# PiInTheSky-Mainboard-v2_4.net
KiCad netlist of a schematic drawn in EAGLE
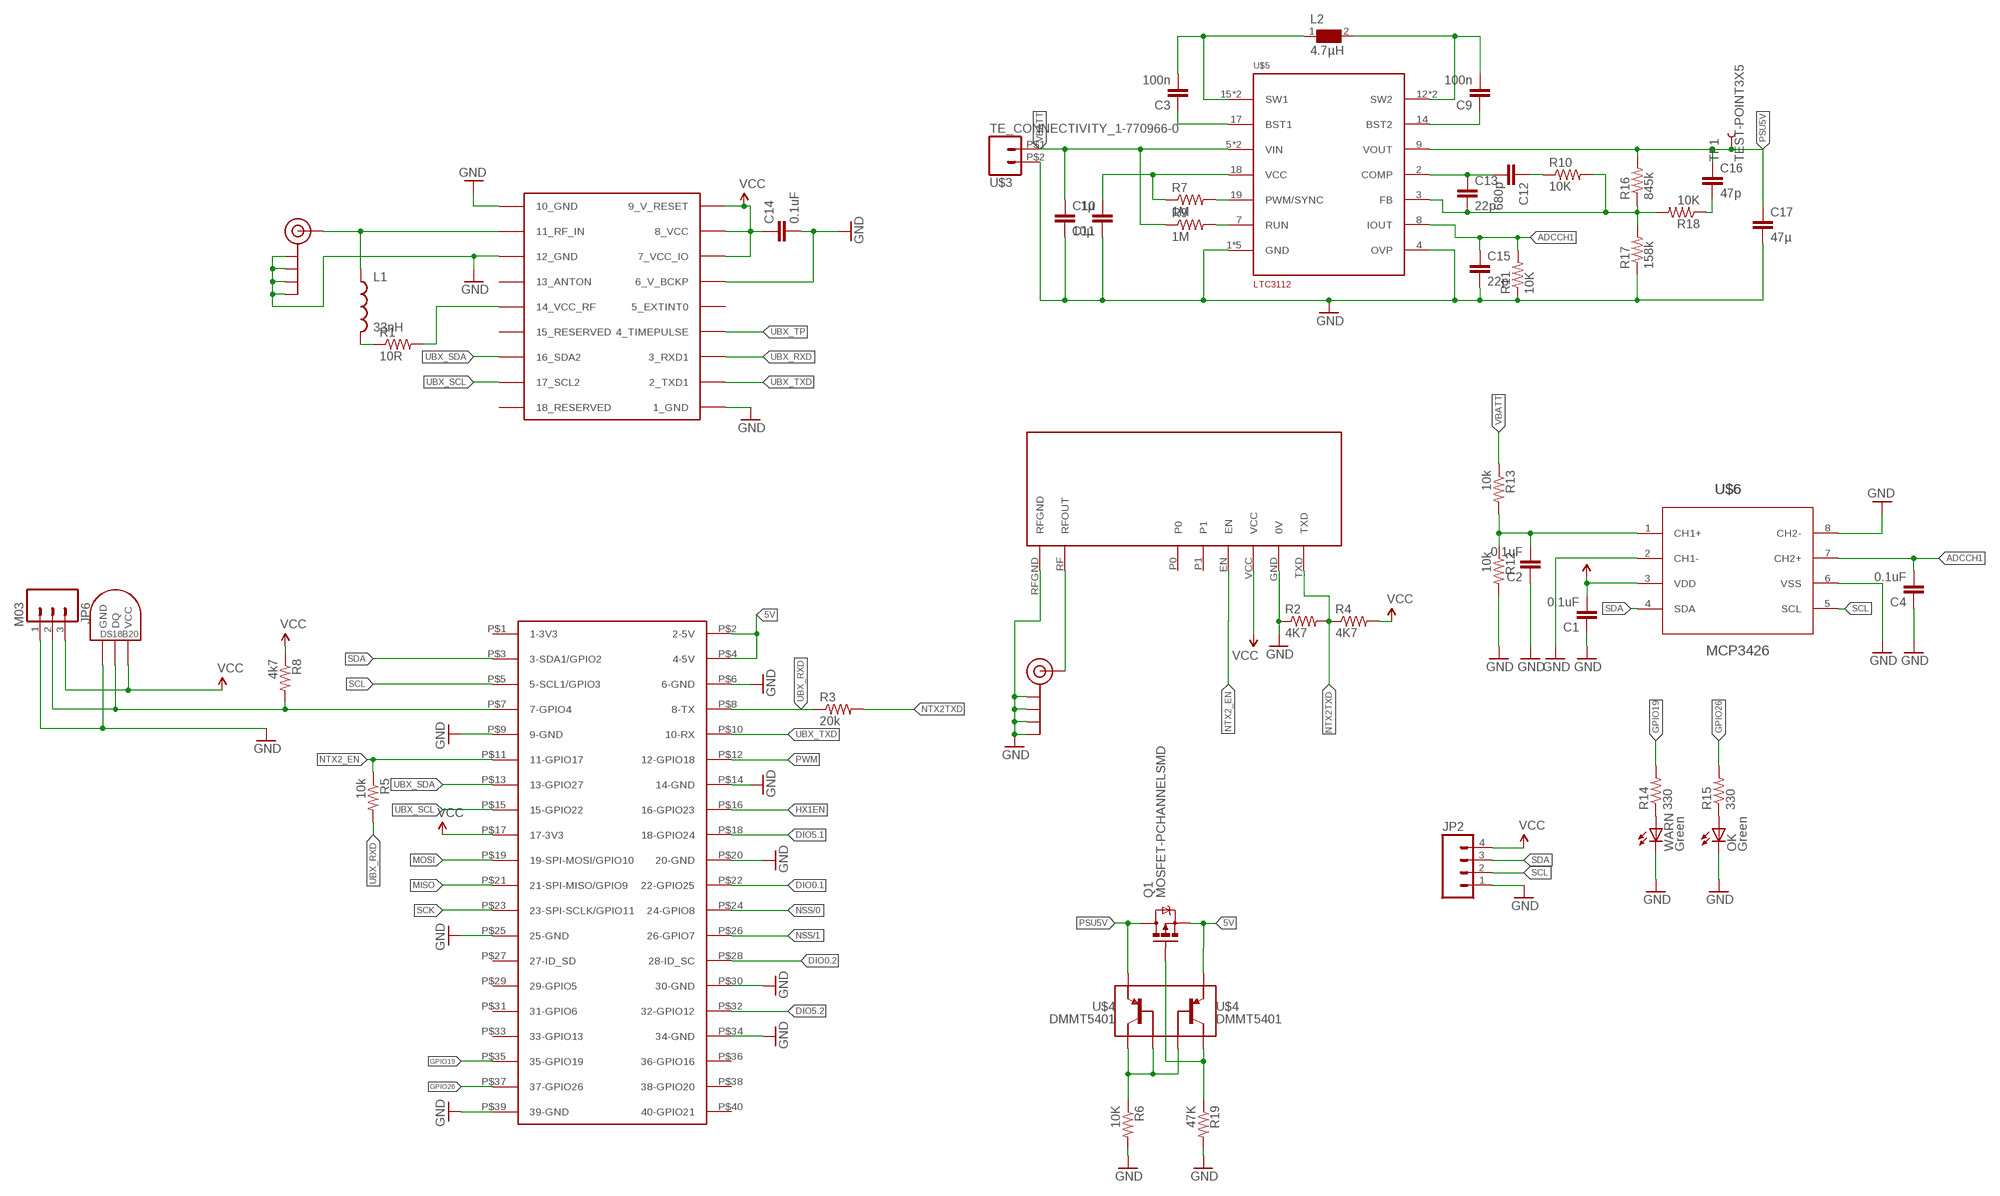
[diagram p0: schematic, sheet 1]

(export (version "E")
  (design (tool "Eeschema 10.0.6"))
  (components
    (comp (ref "C1")
      (value "0.1uF")
      (footprint "eagle-import:0603-CAP")
      (libsource (lib "eagle-import") (part "CAP0603-CAP"))
    )
    (comp (ref "C2")
      (value "0.1uF")
      (footprint "eagle-import:0603-CAP")
      (libsource (lib "eagle-import") (part "CAP0603-CAP"))
    )
    (comp (ref "C3")
      (value "100n")
      (footprint "eagle-import:0603-CAP")
      (libsource (lib "eagle-import") (part "CAP0603-CAP"))
    )
    (comp (ref "C4")
      (value "0.1uF")
      (footprint "eagle-import:0603-CAP")
      (libsource (lib "eagle-import") (part "CAP0603-CAP"))
    )
    (comp (ref "C9")
      (value "100n")
      (footprint "eagle-import:0603-CAP")
      (libsource (lib "eagle-import") (part "CAP0603-CAP"))
    )
    (comp (ref "C10")
      (value "10µ")
      (footprint "eagle-import:1206")
      (libsource (lib "eagle-import") (part "CAP1206"))
    )
    (comp (ref "C11")
      (value "1µ")
      (footprint "eagle-import:0603-CAP")
      (libsource (lib "eagle-import") (part "CAP0603-CAP"))
    )
    (comp (ref "C12")
      (value "680p")
      (footprint "eagle-import:0603-CAP")
      (libsource (lib "eagle-import") (part "CAP0603-CAP"))
    )
    (comp (ref "C13")
      (value "22p")
      (footprint "eagle-import:0603-CAP")
      (libsource (lib "eagle-import") (part "CAP0603-CAP"))
    )
    (comp (ref "C14")
      (value "0.1uF")
      (footprint "eagle-import:0603-CAP")
      (libsource (lib "eagle-import") (part "CAP0603-CAP"))
    )
    (comp (ref "C15")
      (value "22p")
      (footprint "eagle-import:0603-CAP")
      (libsource (lib "eagle-import") (part "CAP0603-CAP"))
    )
    (comp (ref "C16")
      (value "47p")
      (footprint "eagle-import:0603-CAP")
      (libsource (lib "eagle-import") (part "CAP0603-CAP"))
    )
    (comp (ref "C17")
      (value "47µ")
      (footprint "eagle-import:1206")
      (libsource (lib "eagle-import") (part "CAP1206"))
    )
    (comp (ref "J$1")
      (value "SMA_EDGE")
      (footprint "eagle-import:SMA-EDGE")
      (libsource (lib "eagle-import") (part "SMA_EDGE"))
    )
    (comp (ref "J$2")
      (value "SMA_EDGE")
      (footprint "eagle-import:SMA-EDGE")
      (libsource (lib "eagle-import") (part "SMA_EDGE"))
    )
    (comp (ref "JP2")
      (value "M04PTH")
      (footprint "eagle-import:1X04")
      (libsource (lib "eagle-import") (part "M04PTH"))
    )
    (comp (ref "JP6")
      (value "M03")
      (footprint "eagle-import:M03-JST")
      (libsource (lib "eagle-import") (part "M03"))
    )
    (comp (ref "L1")
      (value "33nH")
      (footprint "eagle-import:0603")
      (libsource (lib "eagle-import") (part "INDUCTOR0603"))
    )
    (comp (ref "L2")
      (value "4.7µH")
      (footprint "eagle-import:WE-HCI_7030_7040_7050")
      (fields (field (name "MPN") "744311470"))
      (libsource (lib "eagle-import") (part "WE-HCI_7030/7040/7050-744311470"))
    )
    (comp (ref "OK")
      (value "Green")
      (footprint "eagle-import:LED-0603")
      (libsource (lib "eagle-import") (part "LED0603"))
    )
    (comp (ref "Q1")
      (value "MOSFET-PCHANNELSMD")
      (footprint "eagle-import:SOT23-3")
      (libsource (lib "eagle-import") (part "MOSFET-PCHANNELSMD"))
    )
    (comp (ref "R1")
      (value "10R")
      (footprint "eagle-import:0603-RES")
      (libsource (lib "eagle-import") (part "RESISTOR0603-RES"))
    )
    (comp (ref "R2")
      (value "4K7")
      (footprint "eagle-import:0603-RES")
      (libsource (lib "eagle-import") (part "RESISTOR0603-RES"))
    )
    (comp (ref "R3")
      (value "20k")
      (footprint "eagle-import:0603-RES")
      (libsource (lib "eagle-import") (part "RESISTOR0603-RES"))
    )
    (comp (ref "R4")
      (value "4K7")
      (footprint "eagle-import:0603-RES")
      (libsource (lib "eagle-import") (part "RESISTOR0603-RES"))
    )
    (comp (ref "R5")
      (value "10k")
      (footprint "eagle-import:0603-RES")
      (libsource (lib "eagle-import") (part "RESISTOR0603-RES"))
    )
    (comp (ref "R6")
      (value "10K")
      (footprint "eagle-import:0603-RES")
      (libsource (lib "eagle-import") (part "RESISTOR0603-RES"))
    )
    (comp (ref "R7")
      (value "1M")
      (footprint "eagle-import:0603-RES")
      (libsource (lib "eagle-import") (part "RESISTOR0603-RES"))
    )
    (comp (ref "R8")
      (value "4k7")
      (footprint "eagle-import:0603-RES")
      (libsource (lib "eagle-import") (part "RESISTOR0603-RES"))
    )
    (comp (ref "R9")
      (value "1M")
      (footprint "eagle-import:0603-RES")
      (libsource (lib "eagle-import") (part "RESISTOR0603-RES"))
    )
    (comp (ref "R10")
      (value "10K")
      (footprint "eagle-import:0603-RES")
      (libsource (lib "eagle-import") (part "RESISTOR0603-RES"))
    )
    (comp (ref "R11")
      (value "10K")
      (footprint "eagle-import:0603-RES")
      (libsource (lib "eagle-import") (part "RESISTOR0603-RES"))
    )
    (comp (ref "R12")
      (value "10k")
      (footprint "eagle-import:0603-RES")
      (libsource (lib "eagle-import") (part "RESISTOR0603-RES"))
    )
    (comp (ref "R13")
      (value "10k")
      (footprint "eagle-import:0603-RES")
      (libsource (lib "eagle-import") (part "RESISTOR0603-RES"))
    )
    (comp (ref "R14")
      (value "330")
      (footprint "eagle-import:0603-RES")
      (libsource (lib "eagle-import") (part "RESISTOR0603-RES"))
    )
    (comp (ref "R15")
      (value "330")
      (footprint "eagle-import:0603-RES")
      (libsource (lib "eagle-import") (part "RESISTOR0603-RES"))
    )
    (comp (ref "R16")
      (value "845k")
      (footprint "eagle-import:0603-RES")
      (libsource (lib "eagle-import") (part "RESISTOR0603-RES"))
    )
    (comp (ref "R17")
      (value "158k")
      (footprint "eagle-import:0603-RES")
      (libsource (lib "eagle-import") (part "RESISTOR0603-RES"))
    )
    (comp (ref "R18")
      (value "10K")
      (footprint "eagle-import:0603-RES")
      (libsource (lib "eagle-import") (part "RESISTOR0603-RES"))
    )
    (comp (ref "R19")
      (value "47K")
      (footprint "eagle-import:0603-RES")
      (libsource (lib "eagle-import") (part "RESISTOR0603-RES"))
    )
    (comp (ref "TEMP")
      (value "DS1821")
      (footprint "eagle-import:DS18B20_SOIC")
      (libsource (lib "eagle-import") (part "DS1820SOIC"))
    )
    (comp (ref "TP1")
      (value "TEST-POINT3X5")
      (footprint "eagle-import:PAD.03X.05")
      (libsource (lib "eagle-import") (part "TEST-POINT3X5"))
    )
    (comp (ref "U$1")
      (value "RASPBERRY-PI+")
      (footprint "eagle-import:RASPBERRY-PI-PLUS-CAM_NOTCH")
      (libsource (lib "eagle-import") (part "RASPBERRY-PI+"))
    )
    (comp (ref "U$3")
      (value "TE_CONNECTIVITY_1-770966-0")
      (footprint "eagle-import:TE_CONNECTIVITY_1-770966-0")
      (libsource (lib "eagle-import") (part "TE_CONNECTIVITY_1-770966-0"))
    )
    (comp (ref "U$4")
      (value "DMMT5401")
      (footprint "eagle-import:SOT26")
      (libsource (lib "eagle-import") (part "DMMT5401"))
    )
    (comp (ref "U$5")
      (value "LTC3112")
      (footprint "eagle-import:TSSOP-20")
      (libsource (lib "eagle-import") (part "LTC3112"))
    )
    (comp (ref "U$6")
      (value "MCP3426")
      (footprint "eagle-import:SOIC127P600X175-8N")
      (libsource (lib "eagle-import") (part "MCP3426"))
    )
    (comp (ref "U$7")
      (value "UBLOX_MAX")
      (footprint "eagle-import:UBLOX_MAX")
      (libsource (lib "eagle-import") (part "UBLOX_MAX"))
    )
    (comp (ref "U$8")
      (value "RADIOMETRIX-MTX2")
      (footprint "eagle-import:RADIOMETRIX-MTX2")
      (libsource (lib "eagle-import") (part "RADIOMETRIX-MTX2"))
    )
    (comp (ref "WARN")
      (value "Green")
      (footprint "eagle-import:LED-0603")
      (libsource (lib "eagle-import") (part "LED0603"))
    )
  )
  (nets
    (net (code "1") (name "5V") (class "Default")
      (node (ref "Q1") (pin "2") (pinfunction "S_2") (pintype "passive"))
      (node (ref "U$1") (pin "P$2") (pinfunction "2-5V_P$2") (pintype "bidirectional"))
      (node (ref "U$1") (pin "P$4") (pinfunction "4-5V_P$4") (pintype "bidirectional"))
      (node (ref "U$4") (pin "5") (pinfunction "E2_5") (pintype "passive"))
    )
    (net (code "2") (name "ADCCH1") (class "Default")
      (node (ref "C15") (pin "1") (pinfunction "1_1") (pintype "passive"))
      (node (ref "C4") (pin "2") (pinfunction "2_2") (pintype "passive"))
      (node (ref "R11") (pin "2") (pinfunction "2_2") (pintype "passive"))
      (node (ref "U$5") (pin "8") (pinfunction "IOUT_8") (pintype "bidirectional"))
      (node (ref "U$6") (pin "7") (pinfunction "CH2+_7") (pintype "input"))
    )
    (net (code "3") (name "DIO0.1") (class "Default")
      (node (ref "U$1") (pin "P$22") (pinfunction "22-GPIO25_P$22") (pintype "bidirectional"))
    )
    (net (code "4") (name "DIO0.2") (class "Default")
      (node (ref "U$1") (pin "P$28") (pinfunction "28-ID_SC_P$28") (pintype "bidirectional"))
    )
    (net (code "5") (name "DIO5.1") (class "Default")
      (node (ref "U$1") (pin "P$18") (pinfunction "18-GPIO24_P$18") (pintype "bidirectional"))
    )
    (net (code "6") (name "DIO5.2") (class "Default")
      (node (ref "U$1") (pin "P$32") (pinfunction "32-GPIO12_P$32") (pintype "bidirectional"))
    )
    (net (code "7") (name "GND") (class "Default")
      (node (ref "C1") (pin "1") (pinfunction "1_1") (pintype "passive"))
      (node (ref "C10") (pin "2") (pinfunction "2_2") (pintype "passive"))
      (node (ref "C11") (pin "1") (pinfunction "1_1") (pintype "passive"))
      (node (ref "C14") (pin "2") (pinfunction "2_2") (pintype "passive"))
      (node (ref "C15") (pin "2") (pinfunction "2_2") (pintype "passive"))
      (node (ref "C17") (pin "2") (pinfunction "2_2") (pintype "passive"))
      (node (ref "C2") (pin "1") (pinfunction "1_1") (pintype "passive"))
      (node (ref "C4") (pin "1") (pinfunction "1_1") (pintype "passive"))
      (node (ref "J$1") (pin "GND@0") (pinfunction "GND_GND@0") (pintype "bidirectional"))
      (node (ref "J$1") (pin "GND@1") (pinfunction "GND_GND@1") (pintype "bidirectional"))
      (node (ref "J$1") (pin "GND@2") (pinfunction "GND_GND@2") (pintype "bidirectional"))
      (node (ref "J$1") (pin "GND@3") (pinfunction "GND_GND@3") (pintype "bidirectional"))
      (node (ref "J$2") (pin "GND@0") (pinfunction "GND_GND@0") (pintype "bidirectional"))
      (node (ref "J$2") (pin "GND@1") (pinfunction "GND_GND@1") (pintype "bidirectional"))
      (node (ref "J$2") (pin "GND@2") (pinfunction "GND_GND@2") (pintype "bidirectional"))
      (node (ref "J$2") (pin "GND@3") (pinfunction "GND_GND@3") (pintype "bidirectional"))
      (node (ref "JP2") (pin "1") (pinfunction "1_1") (pintype "passive"))
      (node (ref "JP6") (pin "1") (pinfunction "1_1") (pintype "passive"))
      (node (ref "OK") (pin "C") (pinfunction "C_C") (pintype "passive"))
      (node (ref "R11") (pin "1") (pinfunction "1_1") (pintype "passive"))
      (node (ref "R12") (pin "2") (pinfunction "2_2") (pintype "passive"))
      (node (ref "R17") (pin "1") (pinfunction "1_1") (pintype "passive"))
      (node (ref "R19") (pin "2") (pinfunction "2_2") (pintype "passive"))
      (node (ref "R2") (pin "1") (pinfunction "1_1") (pintype "passive"))
      (node (ref "R6") (pin "2") (pinfunction "2_2") (pintype "passive"))
      (node (ref "TEMP") (pin "GND") (pinfunction "GND_GND") (pintype "power_in"))
      (node (ref "U$1") (pin "P$14") (pinfunction "14-GND_P$14") (pintype "bidirectional"))
      (node (ref "U$1") (pin "P$20") (pinfunction "20-GND_P$20") (pintype "bidirectional"))
      (node (ref "U$1") (pin "P$25") (pinfunction "25-GND_P$25") (pintype "bidirectional"))
      (node (ref "U$1") (pin "P$30") (pinfunction "30-GND_P$30") (pintype "bidirectional"))
      (node (ref "U$1") (pin "P$34") (pinfunction "34-GND_P$34") (pintype "bidirectional"))
      (node (ref "U$1") (pin "P$39") (pinfunction "39-GND_P$39") (pintype "bidirectional"))
      (node (ref "U$1") (pin "P$6") (pinfunction "6-GND_P$6") (pintype "bidirectional"))
      (node (ref "U$1") (pin "P$9") (pinfunction "9-GND_P$9") (pintype "bidirectional"))
      (node (ref "U$3") (pin "P$2") (pinfunction "2_P$2") (pintype "passive"))
      (node (ref "U$5") (pin "1") (pinfunction "GND_1") (pintype "bidirectional"))
      (node (ref "U$5") (pin "10") (pinfunction "GND_10") (pintype "bidirectional"))
      (node (ref "U$5") (pin "11") (pinfunction "GND_11") (pintype "bidirectional"))
      (node (ref "U$5") (pin "20") (pinfunction "GND_20") (pintype "bidirectional"))
      (node (ref "U$5") (pin "21") (pinfunction "GND_21") (pintype "bidirectional"))
      (node (ref "U$5") (pin "4") (pinfunction "OVP_4") (pintype "bidirectional"))
      (node (ref "U$6") (pin "2") (pinfunction "CH1-_2") (pintype "input"))
      (node (ref "U$6") (pin "6") (pinfunction "VSS_6") (pintype "power_in"))
      (node (ref "U$6") (pin "8") (pinfunction "CH2-_8") (pintype "input"))
      (node (ref "U$7") (pin "10_GND") (pinfunction "10_GND_10_GND") (pintype "power_in"))
      (node (ref "U$7") (pin "12_GND") (pinfunction "12_GND_12_GND") (pintype "power_in"))
      (node (ref "U$7") (pin "1_GND") (pinfunction "1_GND_1_GND") (pintype "power_in"))
      (node (ref "U$7") (pin "6_V_BCKP") (pinfunction "6_V_BCKP_6_V_BCKP") (pintype "bidirectional"))
      (node (ref "U$8") (pin "GND") (pinfunction "0V_GND") (pintype "bidirectional"))
      (node (ref "U$8") (pin "RFGND") (pinfunction "RFGND_RFGND") (pintype "bidirectional"))
      (node (ref "WARN") (pin "C") (pinfunction "C_C") (pintype "passive"))
    )
    (net (code "8") (name "GPIO19") (class "Default")
      (node (ref "R14") (pin "2") (pinfunction "2_2") (pintype "passive"))
      (node (ref "U$1") (pin "P$35") (pinfunction "35-GPIO19_P$35") (pintype "bidirectional"))
    )
    (net (code "9") (name "GPIO26") (class "Default")
      (node (ref "R15") (pin "2") (pinfunction "2_2") (pintype "passive"))
      (node (ref "U$1") (pin "P$37") (pinfunction "37-GPIO26_P$37") (pintype "bidirectional"))
    )
    (net (code "10") (name "HX1EN") (class "Default")
      (node (ref "U$1") (pin "P$16") (pinfunction "16-GPIO23_P$16") (pintype "bidirectional"))
    )
    (net (code "11") (name "MISO") (class "Default")
      (node (ref "U$1") (pin "P$21") (pinfunction "21-SPI-MISO/GPIO9_P$21") (pintype "bidirectional"))
    )
    (net (code "12") (name "MOSI") (class "Default")
      (node (ref "U$1") (pin "P$19") (pinfunction "19-SPI-MOSI/GPIO10_P$19") (pintype "bidirectional"))
    )
    (net (code "13") (name "NSS{slash}0") (class "Default")
      (node (ref "U$1") (pin "P$24") (pinfunction "24-GPIO8_P$24") (pintype "bidirectional"))
    )
    (net (code "14") (name "NSS{slash}1") (class "Default")
      (node (ref "U$1") (pin "P$26") (pinfunction "26-GPIO7_P$26") (pintype "bidirectional"))
    )
    (net (code "15") (name "NTX2TXD") (class "Default")
      (node (ref "R2") (pin "2") (pinfunction "2_2") (pintype "passive"))
      (node (ref "R3") (pin "2") (pinfunction "2_2") (pintype "passive"))
      (node (ref "R4") (pin "1") (pinfunction "1_1") (pintype "passive"))
      (node (ref "U$8") (pin "TXD") (pinfunction "TXD_TXD") (pintype "bidirectional"))
    )
    (net (code "16") (name "NTX2_EN") (class "Default")
      (node (ref "R5") (pin "1") (pinfunction "1_1") (pintype "passive"))
      (node (ref "U$1") (pin "P$11") (pinfunction "11-GPIO17_P$11") (pintype "bidirectional"))
      (node (ref "U$8") (pin "EN") (pinfunction "EN_EN") (pintype "bidirectional"))
    )
    (net (code "17") (name "Net-(C3-Pad2)") (class "Default")
      (node (ref "C3") (pin "2") (pinfunction "2_2") (pintype "passive"))
      (node (ref "L2") (pin "1") (pinfunction "1_1") (pintype "passive"))
      (node (ref "U$5") (pin "15") (pinfunction "SW1_15") (pintype "bidirectional"))
      (node (ref "U$5") (pin "16") (pinfunction "SW1_16") (pintype "bidirectional"))
    )
    (net (code "18") (name "Net-(C9-Pad2)") (class "Default")
      (node (ref "C9") (pin "2") (pinfunction "2_2") (pintype "passive"))
      (node (ref "L2") (pin "2") (pinfunction "2_2") (pintype "passive"))
      (node (ref "U$5") (pin "12") (pinfunction "SW2_12") (pintype "bidirectional"))
      (node (ref "U$5") (pin "13") (pinfunction "SW2_13") (pintype "bidirectional"))
    )
    (net (code "19") (name "Net-(C12-Pad1)") (class "Default")
      (node (ref "C12") (pin "1") (pinfunction "1_1") (pintype "passive"))
      (node (ref "R10") (pin "1") (pinfunction "1_1") (pintype "passive"))
    )
    (net (code "20") (name "Net-(C16-Pad2)") (class "Default")
      (node (ref "C16") (pin "2") (pinfunction "2_2") (pintype "passive"))
      (node (ref "R18") (pin "1") (pinfunction "1_1") (pintype "passive"))
    )
    (net (code "21") (name "Net-(J$1-SIGNAL)") (class "Default")
      (node (ref "J$1") (pin "SIG") (pinfunction "SIGNAL_SIG") (pintype "bidirectional"))
      (node (ref "L1") (pin "1") (pinfunction "1_1") (pintype "passive"))
      (node (ref "U$7") (pin "11_RF_IN") (pinfunction "11_RF_IN_11_RF_IN") (pintype "bidirectional"))
    )
    (net (code "22") (name "Net-(J$2-SIGNAL)") (class "Default")
      (node (ref "J$2") (pin "SIG") (pinfunction "SIGNAL_SIG") (pintype "bidirectional"))
      (node (ref "U$8") (pin "RF") (pinfunction "RFOUT_RF") (pintype "bidirectional"))
    )
    (net (code "23") (name "Net-(L1-Pad2)") (class "Default")
      (node (ref "L1") (pin "2") (pinfunction "2_2") (pintype "passive"))
      (node (ref "R1") (pin "1") (pinfunction "1_1") (pintype "passive"))
    )
    (net (code "24") (name "Net-(OK-PadA)") (class "Default")
      (node (ref "OK") (pin "A") (pinfunction "A_A") (pintype "passive"))
      (node (ref "R15") (pin "1") (pinfunction "1_1") (pintype "passive"))
    )
    (net (code "25") (name "Net-(Q1-G)") (class "Default")
      (node (ref "Q1") (pin "1") (pinfunction "G_1") (pintype "passive"))
      (node (ref "R19") (pin "1") (pinfunction "1_1") (pintype "passive"))
      (node (ref "U$4") (pin "4") (pinfunction "C2_4") (pintype "passive"))
    )
    (net (code "26") (name "Net-(R1-Pad2)") (class "Default")
      (node (ref "R1") (pin "2") (pinfunction "2_2") (pintype "passive"))
      (node (ref "U$7") (pin "14_VCC_RF") (pinfunction "14_VCC_RF_14_VCC_RF") (pintype "bidirectional"))
    )
    (net (code "27") (name "Net-(R14-Pad1)") (class "Default")
      (node (ref "R14") (pin "1") (pinfunction "1_1") (pintype "passive"))
      (node (ref "WARN") (pin "A") (pinfunction "A_A") (pintype "passive"))
    )
    (net (code "28") (name "Net-(U$1-7-GPIO4)") (class "Default")
      (node (ref "JP6") (pin "2") (pinfunction "2_2") (pintype "passive"))
      (node (ref "R8") (pin "2") (pinfunction "2_2") (pintype "passive"))
      (node (ref "TEMP") (pin "DQ") (pinfunction "DQ_DQ") (pintype "bidirectional"))
      (node (ref "U$1") (pin "P$7") (pinfunction "7-GPIO4_P$7") (pintype "bidirectional"))
    )
    (net (code "29") (name "Net-(U$4-B1)") (class "Default")
      (node (ref "R6") (pin "1") (pinfunction "1_1") (pintype "passive"))
      (node (ref "U$4") (pin "1") (pinfunction "C1_1") (pintype "passive"))
      (node (ref "U$4") (pin "2") (pinfunction "B1_2") (pintype "passive"))
      (node (ref "U$4") (pin "3") (pinfunction "B2_3") (pintype "passive"))
    )
    (net (code "30") (name "Net-(U$5-BST1)") (class "Default")
      (node (ref "C3") (pin "1") (pinfunction "1_1") (pintype "passive"))
      (node (ref "U$5") (pin "17") (pinfunction "BST1_17") (pintype "bidirectional"))
    )
    (net (code "31") (name "Net-(U$5-BST2)") (class "Default")
      (node (ref "C9") (pin "1") (pinfunction "1_1") (pintype "passive"))
      (node (ref "U$5") (pin "14") (pinfunction "BST2_14") (pintype "bidirectional"))
    )
    (net (code "32") (name "Net-(U$5-COMP)") (class "Default")
      (node (ref "C12") (pin "2") (pinfunction "2_2") (pintype "passive"))
      (node (ref "C13") (pin "1") (pinfunction "1_1") (pintype "passive"))
      (node (ref "U$5") (pin "2") (pinfunction "COMP_2") (pintype "bidirectional"))
    )
    (net (code "33") (name "Net-(U$5-FB)") (class "Default")
      (node (ref "C13") (pin "2") (pinfunction "2_2") (pintype "passive"))
      (node (ref "R10") (pin "2") (pinfunction "2_2") (pintype "passive"))
      (node (ref "R16") (pin "1") (pinfunction "1_1") (pintype "passive"))
      (node (ref "R17") (pin "2") (pinfunction "2_2") (pintype "passive"))
      (node (ref "R18") (pin "2") (pinfunction "2_2") (pintype "passive"))
      (node (ref "U$5") (pin "3") (pinfunction "FB_3") (pintype "bidirectional"))
    )
    (net (code "34") (name "Net-(U$5-PWM{slash}SYNC)") (class "Default")
      (node (ref "R7") (pin "2") (pinfunction "2_2") (pintype "passive"))
      (node (ref "U$5") (pin "19") (pinfunction "PWM/SYNC_19") (pintype "bidirectional"))
    )
    (net (code "35") (name "Net-(U$5-RUN)") (class "Default")
      (node (ref "R9") (pin "2") (pinfunction "2_2") (pintype "passive"))
      (node (ref "U$5") (pin "7") (pinfunction "RUN_7") (pintype "bidirectional"))
    )
    (net (code "36") (name "Net-(U$5-VCC)") (class "Default")
      (node (ref "C11") (pin "2") (pinfunction "2_2") (pintype "passive"))
      (node (ref "R7") (pin "1") (pinfunction "1_1") (pintype "passive"))
      (node (ref "U$5") (pin "18") (pinfunction "VCC_18") (pintype "bidirectional"))
    )
    (net (code "37") (name "Net-(U$6-CH1+)") (class "Default")
      (node (ref "C2") (pin "2") (pinfunction "2_2") (pintype "passive"))
      (node (ref "R12") (pin "1") (pinfunction "1_1") (pintype "passive"))
      (node (ref "R13") (pin "2") (pinfunction "2_2") (pintype "passive"))
      (node (ref "U$6") (pin "1") (pinfunction "CH1+_1") (pintype "power_in"))
    )
    (net (code "38") (name "PSU5V") (class "Default")
      (node (ref "C16") (pin "1") (pinfunction "1_1") (pintype "passive"))
      (node (ref "C17") (pin "1") (pinfunction "1_1") (pintype "passive"))
      (node (ref "Q1") (pin "3") (pinfunction "D_3") (pintype "passive"))
      (node (ref "R16") (pin "2") (pinfunction "2_2") (pintype "passive"))
      (node (ref "TP1") (pin "P$1") (pinfunction "1_P$1") (pintype "bidirectional"))
      (node (ref "U$4") (pin "6") (pinfunction "E1_6") (pintype "passive"))
      (node (ref "U$5") (pin "9") (pinfunction "VOUT_9") (pintype "bidirectional"))
    )
    (net (code "39") (name "PWM") (class "Default")
      (node (ref "U$1") (pin "P$12") (pinfunction "12-GPIO18_P$12") (pintype "bidirectional"))
    )
    (net (code "40") (name "SCK") (class "Default")
      (node (ref "U$1") (pin "P$23") (pinfunction "23-SPI-SCLK/GPIO11_P$23") (pintype "bidirectional"))
    )
    (net (code "41") (name "SCL") (class "Default")
      (node (ref "JP2") (pin "2") (pinfunction "2_2") (pintype "passive"))
      (node (ref "U$1") (pin "P$5") (pinfunction "5-SCL1/GPIO3_P$5") (pintype "bidirectional"))
      (node (ref "U$6") (pin "5") (pinfunction "SCL_5") (pintype "output"))
    )
    (net (code "42") (name "SDA") (class "Default")
      (node (ref "JP2") (pin "3") (pinfunction "3_3") (pintype "passive"))
      (node (ref "U$1") (pin "P$3") (pinfunction "3-SDA1/GPIO2_P$3") (pintype "bidirectional"))
      (node (ref "U$6") (pin "4") (pinfunction "SDA_4") (pintype "input"))
    )
    (net (code "43") (name "UBX_RXD") (class "Default")
      (node (ref "R3") (pin "1") (pinfunction "1_1") (pintype "passive"))
      (node (ref "R5") (pin "2") (pinfunction "2_2") (pintype "passive"))
      (node (ref "U$1") (pin "P$8") (pinfunction "8-TX_P$8") (pintype "bidirectional"))
      (node (ref "U$7") (pin "3_RXD1") (pinfunction "3_RXD1_3_RXD1") (pintype "bidirectional"))
    )
    (net (code "44") (name "UBX_SCL") (class "Default")
      (node (ref "U$1") (pin "P$15") (pinfunction "15-GPIO22_P$15") (pintype "bidirectional"))
      (node (ref "U$7") (pin "17_SCL2") (pinfunction "17_SCL2_17_SCL2") (pintype "bidirectional"))
    )
    (net (code "45") (name "UBX_SDA") (class "Default")
      (node (ref "U$1") (pin "P$13") (pinfunction "13-GPIO27_P$13") (pintype "bidirectional"))
      (node (ref "U$7") (pin "16_SDA2") (pinfunction "16_SDA2_16_SDA2") (pintype "bidirectional"))
    )
    (net (code "46") (name "UBX_TP") (class "Default")
      (node (ref "U$7") (pin "4_TIMEPULSE") (pinfunction "4_TIMEPULSE_4_TIMEPULSE") (pintype "bidirectional"))
    )
    (net (code "47") (name "UBX_TXD") (class "Default")
      (node (ref "U$1") (pin "P$10") (pinfunction "10-RX_P$10") (pintype "bidirectional"))
      (node (ref "U$7") (pin "2_TXD1") (pinfunction "2_TXD1_2_TXD1") (pintype "bidirectional"))
    )
    (net (code "48") (name "VBATT") (class "Default")
      (node (ref "C10") (pin "1") (pinfunction "1_1") (pintype "passive"))
      (node (ref "R13") (pin "1") (pinfunction "1_1") (pintype "passive"))
      (node (ref "R9") (pin "1") (pinfunction "1_1") (pintype "passive"))
      (node (ref "U$3") (pin "P$1") (pinfunction "1_P$1") (pintype "passive"))
      (node (ref "U$5") (pin "5") (pinfunction "VIN_5") (pintype "bidirectional"))
      (node (ref "U$5") (pin "6") (pinfunction "VIN_6") (pintype "bidirectional"))
    )
    (net (code "49") (name "VCC") (class "Default")
      (node (ref "C1") (pin "2") (pinfunction "2_2") (pintype "passive"))
      (node (ref "C14") (pin "1") (pinfunction "1_1") (pintype "passive"))
      (node (ref "JP2") (pin "4") (pinfunction "4_4") (pintype "passive"))
      (node (ref "JP6") (pin "3") (pinfunction "3_3") (pintype "passive"))
      (node (ref "R4") (pin "2") (pinfunction "2_2") (pintype "passive"))
      (node (ref "R8") (pin "1") (pinfunction "1_1") (pintype "passive"))
      (node (ref "TEMP") (pin "VCC") (pinfunction "VCC_VCC") (pintype "power_in"))
      (node (ref "U$1") (pin "P$17") (pinfunction "17-3V3_P$17") (pintype "bidirectional"))
      (node (ref "U$6") (pin "3") (pinfunction "VDD_3") (pintype "input"))
      (node (ref "U$7") (pin "7_VCC_IO") (pinfunction "7_VCC_IO_7_VCC_IO") (pintype "power_in"))
      (node (ref "U$7") (pin "8_VCC") (pinfunction "8_VCC_8_VCC") (pintype "power_in"))
      (node (ref "U$7") (pin "9_V_RESET") (pinfunction "9_V_RESET_9_V_RESET") (pintype "power_in"))
      (node (ref "U$8") (pin "VCC") (pinfunction "VCC_VCC") (pintype "bidirectional"))
    )
    (net (code "50") (name "unconnected-(U$1-1-3V3-PadP$1)") (class "Default")
      (node (ref "U$1") (pin "P$1") (pinfunction "1-3V3_P$1") (pintype "bidirectional"))
    )
    (net (code "51") (name "unconnected-(U$1-27-ID_SD-PadP$27)") (class "Default")
      (node (ref "U$1") (pin "P$27") (pinfunction "27-ID_SD_P$27") (pintype "bidirectional"))
    )
    (net (code "52") (name "unconnected-(U$1-29-GPIO5-PadP$29)") (class "Default")
      (node (ref "U$1") (pin "P$29") (pinfunction "29-GPIO5_P$29") (pintype "bidirectional"))
    )
    (net (code "53") (name "unconnected-(U$1-31-GPIO6-PadP$31)") (class "Default")
      (node (ref "U$1") (pin "P$31") (pinfunction "31-GPIO6_P$31") (pintype "bidirectional"))
    )
    (net (code "54") (name "unconnected-(U$1-33-GPIO13-PadP$33)") (class "Default")
      (node (ref "U$1") (pin "P$33") (pinfunction "33-GPIO13_P$33") (pintype "bidirectional"))
    )
    (net (code "55") (name "unconnected-(U$1-36-GPIO16-PadP$36)") (class "Default")
      (node (ref "U$1") (pin "P$36") (pinfunction "36-GPIO16_P$36") (pintype "bidirectional"))
    )
    (net (code "56") (name "unconnected-(U$1-38-GPIO20-PadP$38)") (class "Default")
      (node (ref "U$1") (pin "P$38") (pinfunction "38-GPIO20_P$38") (pintype "bidirectional"))
    )
    (net (code "57") (name "unconnected-(U$1-40-GPIO21-PadP$40)") (class "Default")
      (node (ref "U$1") (pin "P$40") (pinfunction "40-GPIO21_P$40") (pintype "bidirectional"))
    )
    (net (code "58") (name "unconnected-(U$7-Pad5_EXTINT0)") (class "Default")
      (node (ref "U$7") (pin "5_EXTINT0") (pinfunction "5_EXTINT0_5_EXTINT0") (pintype "bidirectional"))
    )
    (net (code "59") (name "unconnected-(U$7-Pad13_ANTON)") (class "Default")
      (node (ref "U$7") (pin "13_ANTON") (pinfunction "13_ANTON_13_ANTON") (pintype "bidirectional"))
    )
    (net (code "60") (name "unconnected-(U$7-Pad15_RESERVED)") (class "Default")
      (node (ref "U$7") (pin "15_RESERVED") (pinfunction "15_RESERVED_15_RESERVED") (pintype "bidirectional"))
    )
    (net (code "61") (name "unconnected-(U$7-Pad18_RESERVED)") (class "Default")
      (node (ref "U$7") (pin "18_RESERVED") (pinfunction "18_RESERVED_18_RESERVED") (pintype "bidirectional"))
    )
    (net (code "62") (name "unconnected-(U$8-PadP0)") (class "Default")
      (node (ref "U$8") (pin "P0") (pinfunction "P0_P0") (pintype "bidirectional"))
    )
    (net (code "63") (name "unconnected-(U$8-PadP1)") (class "Default")
      (node (ref "U$8") (pin "P1") (pinfunction "P1_P1") (pintype "bidirectional"))
    )
  )
)
